# RPi_PICO.net
KiCad netlist of a schematic drawn in Altium Designer
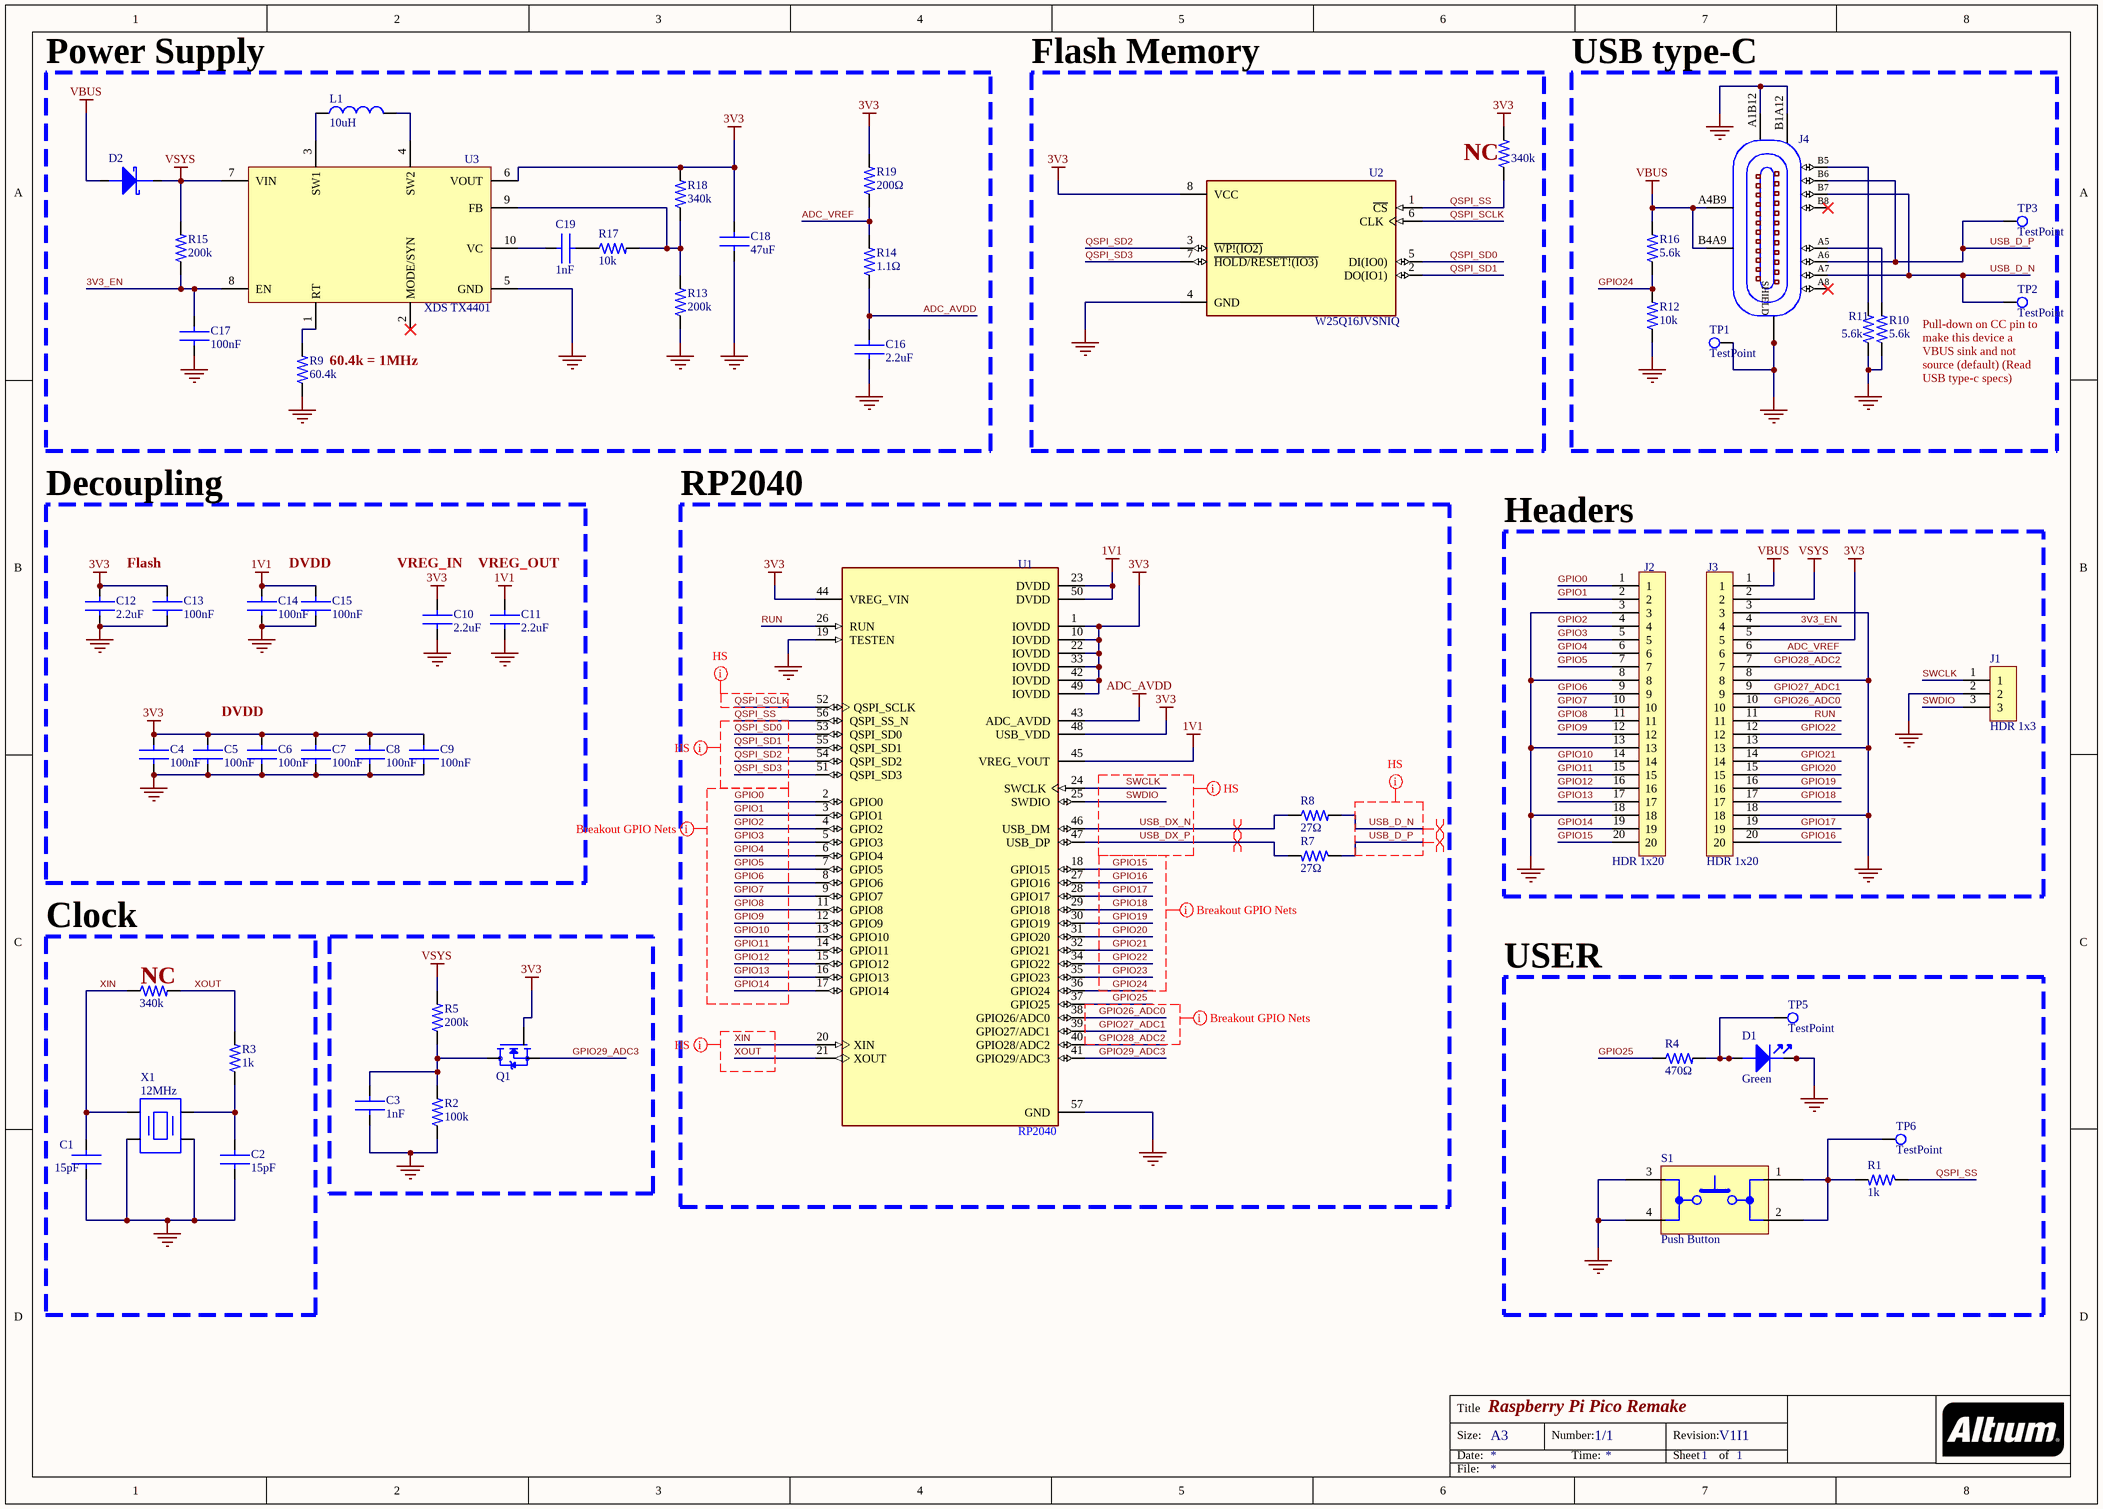
[diagram p0: RPi_PICO.SchDoc]

(export (version "E")
  (design (tool "Eeschema 10.0.6"))
  (components
    (comp (ref "C1")
      (value "15pF")
      (footprint "MLCC-0201")
      (description "15pF ±5% 50V 0201 C0G MLCC - SMD/SMT ROHS")
      (libsource (lib "RPi_PICO") (part "0201CG150J500NT"))
    )
    (comp (ref "C2")
      (value "15pF")
      (footprint "MLCC-0201")
      (description "15pF ±5% 50V 0201 C0G MLCC - SMD/SMT ROHS")
      (libsource (lib "RPi_PICO") (part "0201CG150J500NT"))
    )
    (comp (ref "C3")
      (value "1nF")
      (footprint "MLCC-0201")
      (description "1nF ±10% 50V 0201  X7R  MLCC - SMD/SMT ROHS")
      (libsource (lib "RPi_PICO") (part "CC0201KRX7R9BB102"))
    )
    (comp (ref "C4")
      (value "100nF")
      (footprint "MLCC-0201")
      (description "100nF ±10% 10V 0201 X5R MLCC - SMD/SMT ROHS")
      (libsource (lib "RPi_PICO") (part "CL03A104KP3NNNC"))
    )
    (comp (ref "C5")
      (value "100nF")
      (footprint "MLCC-0201")
      (description "100nF ±10% 10V 0201 X5R MLCC - SMD/SMT ROHS")
      (libsource (lib "RPi_PICO") (part "CL03A104KP3NNNC"))
    )
    (comp (ref "C6")
      (value "100nF")
      (footprint "MLCC-0201")
      (description "100nF ±10% 10V 0201 X5R MLCC - SMD/SMT ROHS")
      (libsource (lib "RPi_PICO") (part "CL03A104KP3NNNC"))
    )
    (comp (ref "C7")
      (value "100nF")
      (footprint "MLCC-0201")
      (description "100nF ±10% 10V 0201 X5R MLCC - SMD/SMT ROHS")
      (libsource (lib "RPi_PICO") (part "CL03A104KP3NNNC"))
    )
    (comp (ref "C8")
      (value "100nF")
      (footprint "MLCC-0201")
      (description "100nF ±10% 10V 0201 X5R MLCC - SMD/SMT ROHS")
      (libsource (lib "RPi_PICO") (part "CL03A104KP3NNNC"))
    )
    (comp (ref "C9")
      (value "100nF")
      (footprint "MLCC-0201")
      (description "100nF ±10% 10V 0201 X5R MLCC - SMD/SMT ROHS")
      (libsource (lib "RPi_PICO") (part "CL03A104KP3NNNC"))
    )
    (comp (ref "C10")
      (value "2.2uF")
      (footprint "MLCC-0402")
      (description "2.2uF ±20% 6.3V 0402 X5R   MLCC - SMD/SMT ROHS")
      (libsource (lib "RPi_PICO") (part "CL05A225MQ5NSNC"))
    )
    (comp (ref "C11")
      (value "2.2uF")
      (footprint "MLCC-0402")
      (description "2.2uF ±20% 6.3V 0402 X5R   MLCC - SMD/SMT ROHS")
      (libsource (lib "RPi_PICO") (part "CL05A225MQ5NSNC"))
    )
    (comp (ref "C12")
      (value "2.2uF")
      (footprint "MLCC-0402")
      (description "2.2uF ±20% 6.3V 0402 X5R   MLCC - SMD/SMT ROHS")
      (libsource (lib "RPi_PICO") (part "CL05A225MQ5NSNC"))
    )
    (comp (ref "C13")
      (value "100nF")
      (footprint "MLCC-0201")
      (description "100nF ±10% 10V 0201 X5R MLCC - SMD/SMT ROHS")
      (libsource (lib "RPi_PICO") (part "CL03A104KP3NNNC"))
    )
    (comp (ref "C14")
      (value "100nF")
      (footprint "MLCC-0201")
      (description "100nF ±10% 10V 0201 X5R MLCC - SMD/SMT ROHS")
      (libsource (lib "RPi_PICO") (part "CL03A104KP3NNNC"))
    )
    (comp (ref "C15")
      (value "100nF")
      (footprint "MLCC-0201")
      (description "100nF ±10% 10V 0201 X5R MLCC - SMD/SMT ROHS")
      (libsource (lib "RPi_PICO") (part "CL03A104KP3NNNC"))
    )
    (comp (ref "C16")
      (value "2.2uF")
      (footprint "MLCC-0402")
      (description "2.2uF ±20% 6.3V 0402 X5R   MLCC - SMD/SMT ROHS")
      (libsource (lib "RPi_PICO") (part "CL05A225MQ5NSNC"))
    )
    (comp (ref "C17")
      (value "100nF")
      (footprint "MLCC-0201")
      (description "100nF ±10% 10V 0201 X5R MLCC - SMD/SMT ROHS")
      (libsource (lib "RPi_PICO") (part "CL03A104KP3NNNC"))
    )
    (comp (ref "C18")
      (value "47uF")
      (footprint "Ceramic_0805")
      (description "47uF 6.3V ±20% 0805   X5R MLCC - SMD/SMT ROHS")
      (libsource (lib "RPi_PICO") (part "CL21A476MQYNNNE"))
    )
    (comp (ref "C19")
      (value "1nF")
      (footprint "MLCC-0201")
      (description "1nF ±10% 50V 0201  X7R  MLCC - SMD/SMT ROHS")
      (libsource (lib "RPi_PICO") (part "CC0201KRX7R9BB102"))
    )
    (comp (ref "D1")
      (value "Green")
      (footprint "LED-0603")
      (libsource (lib "RPi_PICO") (part "19-217/GHC-YR1S2/3T"))
    )
    (comp (ref "D2")
      (value "Schottky")
      (footprint "SOD-123F")
      (description "Diode Schottky 20 V 1A Surface Mount SOD-123FL")
      (libsource (lib "HUZZAH32") (part "RB161MM-20CT-ND"))
    )
    (comp (ref "J1")
      (value "HDR 1x3")
      (footprint "CONN-3-SMD+THT")
      (description "HDR 1x3 2.54mm double SMD+THT")
      (libsource (lib "RPi_PICO") (part "HDR 1x3 2.54mm double"))
    )
    (comp (ref "J2")
      (value "HDR 1x20")
      (footprint "Conn-20-SMD+THT")
      (description "HDR 1x20 2.54mm double SMD+THT")
      (libsource (lib "RPi_PICO") (part "HDR 1x20 2.54mm double"))
    )
    (comp (ref "J3")
      (value "HDR 1x20")
      (footprint "Conn-20-SMD+THT")
      (description "HDR 1x20 2.54mm double SMD+THT")
      (libsource (lib "") (part "HDR 1x20 2.54mm double_1"))
    )
    (comp (ref "J4")
      (value "USB-type-c")
      (footprint "USB-type-c-31-M-12")
      (description "250mA 1 16 Female Type-C SMD USB Connectors ROHS")
      (libsource (lib "RPi_PICO") (part "USB-type-c"))
    )
    (comp (ref "L1")
      (value "10uH")
      (footprint "L-1515-SMD")
      (description "1.7A 10uH ±20% 2.5A 165mΩ - Inductors (SMD) ROHS")
      (libsource (lib "RPi_PICO") (part "FDSD0420-H-100M=P3"))
    )
    (comp (ref "Q1") (value "N-MOS") (footprint "SOT-523") (libsource (lib "RPi_PICO") (part "TPCJ1012")))
    (comp (ref "R1") (value "1k") (footprint "R-0402") (libsource (lib "RPi_PICO") (part "0402WGF1001TCE")))
    (comp (ref "R2") (value "100k") (footprint "R-0402") (libsource (lib "RPi_PICO") (part "0402WGF1003TCE")))
    (comp (ref "R3") (value "1k") (footprint "R-0402") (libsource (lib "RPi_PICO") (part "0402WGF1001TCE")))
    (comp (ref "R4") (value "470Ω") (footprint "R-0402") (libsource (lib "RPi_PICO") (part "0402WGF4700TCE")))
    (comp (ref "R5") (value "200k") (footprint "R-0402") (libsource (lib "RPi_PICO") (part "0402WGF2003TCE")))
    (comp (ref "R6") (value "340k") (footprint "R-0402") (libsource (lib "RPi_PICO") (part "WR04X3403FTL")))
    (comp (ref "R7") (value "27Ω") (footprint "R-0201") (libsource (lib "RPi_PICO") (part "RC0201JR-0727RL")))
    (comp (ref "R8") (value "27Ω") (footprint "R-0201") (libsource (lib "RPi_PICO") (part "RC0201JR-0727RL")))
    (comp (ref "R9")
      (value "60.4k")
      (footprint "R-0402")
      (libsource (lib "RPi_PICO") (part "0402WGF6042TCE"))
    )
    (comp (ref "R10")
      (value "5.6k")
      (footprint "R-0402")
      (libsource (lib "RPi_PICO") (part "0402WGF5601TCE"))
    )
    (comp (ref "R11")
      (value "5.6k")
      (footprint "R-0402")
      (libsource (lib "RPi_PICO") (part "0402WGF5601TCE"))
    )
    (comp (ref "R12")
      (value "10k")
      (footprint "R-0402")
      (libsource (lib "RPi_PICO") (part "RC0402FR-0710KL"))
    )
    (comp (ref "R13")
      (value "200k")
      (footprint "R-0402")
      (libsource (lib "RPi_PICO") (part "0402WGF2003TCE"))
    )
    (comp (ref "R14")
      (value "1.1Ω")
      (footprint "R-0402")
      (libsource (lib "RPi_PICO") (part "0402WGJ011JTCE"))
    )
    (comp (ref "R15")
      (value "200k")
      (footprint "R-0402")
      (libsource (lib "RPi_PICO") (part "0402WGF2003TCE"))
    )
    (comp (ref "R16")
      (value "5.6k")
      (footprint "R-0402")
      (libsource (lib "RPi_PICO") (part "0402WGF5601TCE"))
    )
    (comp (ref "R17")
      (value "10k")
      (footprint "R-0402")
      (libsource (lib "RPi_PICO") (part "RC0402FR-0710KL"))
    )
    (comp (ref "R18") (value "340k") (footprint "R-0402") (libsource (lib "RPi_PICO") (part "WR04X3403FTL")))
    (comp (ref "R19")
      (value "200Ω")
      (footprint "R_0603")
      (libsource (lib "RPi_PICO") (part "0603WAF2000T5E"))
    )
    (comp (ref "R20") (value "340k") (footprint "R-0402") (libsource (lib "RPi_PICO") (part "WR04X3403FTL")))
    (comp (ref "S1")
      (value "Push Button")
      (footprint "SW_PB_6643")
      (description "SPST tactile switch SMD 6x6x4.3mm")
      (libsource (lib "HUZZAH32") (part "GT-TC089B-H043-L1"))
    )
    (comp (ref "TP1")
      (value "TestPoint")
      (footprint "TestPoint-60mil-rectangle")
      (libsource (lib "RPi_PICO") (part "TestPoint"))
    )
    (comp (ref "TP2")
      (value "TestPoint")
      (footprint "TestPoint-60mil-rectangle")
      (libsource (lib "RPi_PICO") (part "TestPoint"))
    )
    (comp (ref "TP3")
      (value "TestPoint")
      (footprint "TestPoint-60mil-rectangle")
      (libsource (lib "RPi_PICO") (part "TestPoint"))
    )
    (comp (ref "TP5")
      (value "TestPoint")
      (footprint "TestPoint-60mil-rectangle")
      (libsource (lib "RPi_PICO") (part "TestPoint"))
    )
    (comp (ref "TP6")
      (value "TestPoint")
      (footprint "TestPoint-60mil-rectangle")
      (libsource (lib "RPi_PICO") (part "TestPoint"))
    )
    (comp (ref "U1") (value "RP2040") (footprint "QFN56-RP2040") (libsource (lib "RPi_PICO") (part "RP2040")))
    (comp (ref "U2")
      (value "W25Q16JVSNIQ")
      (footprint "SOIC-8")
      (description "FLASH - NOR Memory IC 16Mb (2M x 8) SPI - Quad I/O 133 MHz SOIC-8")
      (libsource (lib "RPi_PICO") (part "W25Q16JVSNIQ"))
    )
    (comp (ref "U3")
      (value "XDS TX4401")
      (footprint "MSOP-10L")
      (description "Buck-boost type -40℃~+85℃ 1 1.8V~5.5V 2.5V~5.5V 1A 1uA MSOP-10L DC-DC Converters ROHS")
      (libsource (lib "RPi_PICO") (part "XDS-TX4401"))
    )
    (comp (ref "X1")
      (value "12MHz")
      (footprint "XTAL-SMD-3.2mm-2.5mm")
      (description "12MHz HCMOS 1.8V~3.3V -20℃~+70℃ ±30ppm  SMD3225-4P Oscillators ROHS")
      (libsource (lib "RPi_PICO") (part "HCI CO32H4-12.000-WPJHPSN"))
    )
  )
  (nets
    (net (code "1") (name "/3V3_EN") (class "Default")
      (node (ref "C17") (pin "2") (pinfunction "2_2") (pintype "passive"))
      (node (ref "J3") (pin "4") (pinfunction "4_4") (pintype "passive"))
      (node (ref "R15") (pin "1") (pinfunction "1_1") (pintype "passive"))
      (node (ref "U3") (pin "8") (pinfunction "EN_8") (pintype "passive"))
    )
    (net (code "2") (name "/ADC_VREF") (class "Default")
      (node (ref "J3") (pin "6") (pinfunction "6_6") (pintype "passive"))
      (node (ref "R14") (pin "2") (pinfunction "2_2") (pintype "passive"))
      (node (ref "R19") (pin "1") (pinfunction "1_1") (pintype "passive"))
    )
    (net (code "3") (name "/GPIO0") (class "Default")
      (node (ref "J2") (pin "1") (pinfunction "1_1") (pintype "passive"))
      (node (ref "U1") (pin "2") (pinfunction "GPIO0_2") (pintype "bidirectional"))
    )
    (net (code "4") (name "/GPIO1") (class "Default")
      (node (ref "J2") (pin "2") (pinfunction "2_2") (pintype "passive"))
      (node (ref "U1") (pin "3") (pinfunction "GPIO1_3") (pintype "bidirectional"))
    )
    (net (code "5") (name "/GPIO2") (class "Default")
      (node (ref "J2") (pin "4") (pinfunction "4_4") (pintype "passive"))
      (node (ref "U1") (pin "4") (pinfunction "GPIO2_4") (pintype "bidirectional"))
    )
    (net (code "6") (name "/GPIO3") (class "Default")
      (node (ref "J2") (pin "5") (pinfunction "5_5") (pintype "passive"))
      (node (ref "U1") (pin "5") (pinfunction "GPIO3_5") (pintype "bidirectional"))
    )
    (net (code "7") (name "/GPIO4") (class "Default")
      (node (ref "J2") (pin "6") (pinfunction "6_6") (pintype "passive"))
      (node (ref "U1") (pin "6") (pinfunction "GPIO4_6") (pintype "bidirectional"))
    )
    (net (code "8") (name "/GPIO5") (class "Default")
      (node (ref "J2") (pin "7") (pinfunction "7_7") (pintype "passive"))
      (node (ref "U1") (pin "7") (pinfunction "GPIO5_7") (pintype "bidirectional"))
    )
    (net (code "9") (name "/GPIO6") (class "Default")
      (node (ref "J2") (pin "9") (pinfunction "9_9") (pintype "passive"))
      (node (ref "U1") (pin "8") (pinfunction "GPIO6_8") (pintype "bidirectional"))
    )
    (net (code "10") (name "/GPIO7") (class "Default")
      (node (ref "J2") (pin "10") (pinfunction "10_10") (pintype "passive"))
      (node (ref "U1") (pin "9") (pinfunction "GPIO7_9") (pintype "bidirectional"))
    )
    (net (code "11") (name "/GPIO8") (class "Default")
      (node (ref "J2") (pin "11") (pinfunction "11_11") (pintype "passive"))
      (node (ref "U1") (pin "11") (pinfunction "GPIO8_11") (pintype "bidirectional"))
    )
    (net (code "12") (name "/GPIO9") (class "Default")
      (node (ref "J2") (pin "12") (pinfunction "12_12") (pintype "passive"))
      (node (ref "U1") (pin "12") (pinfunction "GPIO9_12") (pintype "bidirectional"))
    )
    (net (code "13") (name "/GPIO10") (class "Default")
      (node (ref "J2") (pin "14") (pinfunction "14_14") (pintype "passive"))
      (node (ref "U1") (pin "13") (pinfunction "GPIO10_13") (pintype "bidirectional"))
    )
    (net (code "14") (name "/GPIO11") (class "Default")
      (node (ref "J2") (pin "15") (pinfunction "15_15") (pintype "passive"))
      (node (ref "U1") (pin "14") (pinfunction "GPIO11_14") (pintype "bidirectional"))
    )
    (net (code "15") (name "/GPIO12") (class "Default")
      (node (ref "J2") (pin "16") (pinfunction "16_16") (pintype "passive"))
      (node (ref "U1") (pin "15") (pinfunction "GPIO12_15") (pintype "bidirectional"))
    )
    (net (code "16") (name "/GPIO13") (class "Default")
      (node (ref "J2") (pin "17") (pinfunction "17_17") (pintype "passive"))
      (node (ref "U1") (pin "16") (pinfunction "GPIO13_16") (pintype "bidirectional"))
    )
    (net (code "17") (name "/GPIO14") (class "Default")
      (node (ref "J2") (pin "19") (pinfunction "19_19") (pintype "passive"))
      (node (ref "U1") (pin "17") (pinfunction "GPIO14_17") (pintype "bidirectional"))
    )
    (net (code "18") (name "/GPIO15") (class "Default")
      (node (ref "J2") (pin "20") (pinfunction "20_20") (pintype "passive"))
      (node (ref "U1") (pin "18") (pinfunction "GPIO15_18") (pintype "bidirectional"))
    )
    (net (code "19") (name "/GPIO16") (class "Default")
      (node (ref "J3") (pin "20") (pinfunction "20_20") (pintype "passive"))
      (node (ref "U1") (pin "27") (pinfunction "GPIO16_27") (pintype "bidirectional"))
    )
    (net (code "20") (name "/GPIO17") (class "Default")
      (node (ref "J3") (pin "19") (pinfunction "19_19") (pintype "passive"))
      (node (ref "U1") (pin "28") (pinfunction "GPIO17_28") (pintype "bidirectional"))
    )
    (net (code "21") (name "/GPIO18") (class "Default")
      (node (ref "J3") (pin "17") (pinfunction "17_17") (pintype "passive"))
      (node (ref "U1") (pin "29") (pinfunction "GPIO18_29") (pintype "bidirectional"))
    )
    (net (code "22") (name "/GPIO19") (class "Default")
      (node (ref "J3") (pin "16") (pinfunction "16_16") (pintype "passive"))
      (node (ref "U1") (pin "30") (pinfunction "GPIO19_30") (pintype "bidirectional"))
    )
    (net (code "23") (name "/GPIO20") (class "Default")
      (node (ref "J3") (pin "15") (pinfunction "15_15") (pintype "passive"))
      (node (ref "U1") (pin "31") (pinfunction "GPIO20_31") (pintype "bidirectional"))
    )
    (net (code "24") (name "/GPIO21") (class "Default")
      (node (ref "J3") (pin "14") (pinfunction "14_14") (pintype "passive"))
      (node (ref "U1") (pin "32") (pinfunction "GPIO21_32") (pintype "bidirectional"))
    )
    (net (code "25") (name "/GPIO22") (class "Default")
      (node (ref "J3") (pin "12") (pinfunction "12_12") (pintype "passive"))
      (node (ref "U1") (pin "34") (pinfunction "GPIO22_34") (pintype "bidirectional"))
    )
    (net (code "26") (name "/GPIO23") (class "Default")
      (node (ref "U1") (pin "35") (pinfunction "GPIO23_35") (pintype "bidirectional"))
    )
    (net (code "27") (name "/GPIO24") (class "Default")
      (node (ref "R12") (pin "2") (pinfunction "2_2") (pintype "passive"))
      (node (ref "R16") (pin "1") (pinfunction "1_1") (pintype "passive"))
      (node (ref "U1") (pin "36") (pinfunction "GPIO24_36") (pintype "bidirectional"))
    )
    (net (code "28") (name "/GPIO25") (class "Default")
      (node (ref "R4") (pin "1") (pinfunction "1_1") (pintype "passive"))
      (node (ref "U1") (pin "37") (pinfunction "GPIO25_37") (pintype "bidirectional"))
    )
    (net (code "29") (name "/GPIO26_ADC0") (class "Default")
      (node (ref "J3") (pin "10") (pinfunction "10_10") (pintype "passive"))
      (node (ref "U1") (pin "38") (pinfunction "GPIO26/ADC0_38") (pintype "bidirectional"))
    )
    (net (code "30") (name "/GPIO27_ADC1") (class "Default")
      (node (ref "J3") (pin "9") (pinfunction "9_9") (pintype "passive"))
      (node (ref "U1") (pin "39") (pinfunction "GPIO27/ADC1_39") (pintype "bidirectional"))
    )
    (net (code "31") (name "/GPIO28_ADC2") (class "Default")
      (node (ref "J3") (pin "7") (pinfunction "7_7") (pintype "passive"))
      (node (ref "U1") (pin "40") (pinfunction "GPIO28/ADC2_40") (pintype "bidirectional"))
    )
    (net (code "32") (name "/GPIO29_ADC3") (class "Default")
      (node (ref "Q1") (pin "3") (pinfunction "S_3") (pintype "passive"))
      (node (ref "U1") (pin "41") (pinfunction "GPIO29/ADC3_41") (pintype "bidirectional"))
    )
    (net (code "33") (name "/QSPI_SCLK") (class "Default")
      (node (ref "U1") (pin "52") (pinfunction "QSPI_SCLK_52") (pintype "bidirectional"))
      (node (ref "U2") (pin "6") (pinfunction "CLK_6") (pintype "input"))
    )
    (net (code "34") (name "/QSPI_SD0") (class "Default")
      (node (ref "U1") (pin "53") (pinfunction "QSPI_SD0_53") (pintype "bidirectional"))
      (node (ref "U2") (pin "5") (pinfunction "DI(IO0)_5") (pintype "bidirectional"))
    )
    (net (code "35") (name "/QSPI_SD1") (class "Default")
      (node (ref "U1") (pin "55") (pinfunction "QSPI_SD1_55") (pintype "bidirectional"))
      (node (ref "U2") (pin "2") (pinfunction "DO(IO1)_2") (pintype "bidirectional"))
    )
    (net (code "36") (name "/QSPI_SD2") (class "Default")
      (node (ref "U1") (pin "54") (pinfunction "QSPI_SD2_54") (pintype "bidirectional"))
      (node (ref "U2") (pin "3") (pinfunction "~{WP!(IO2)}_3") (pintype "bidirectional"))
    )
    (net (code "37") (name "/QSPI_SD3") (class "Default")
      (node (ref "U1") (pin "51") (pinfunction "QSPI_SD3_51") (pintype "bidirectional"))
      (node (ref "U2") (pin "7") (pinfunction "~{HOLD/RESET!(IO3)}_7") (pintype "bidirectional"))
    )
    (net (code "38") (name "/QSPI_SS") (class "Default")
      (node (ref "R1") (pin "1") (pinfunction "1_1") (pintype "passive"))
      (node (ref "R20") (pin "1") (pinfunction "1_1") (pintype "passive"))
      (node (ref "U1") (pin "56") (pinfunction "QSPI_SS_N_56") (pintype "bidirectional"))
      (node (ref "U2") (pin "1") (pinfunction "~{CS}_1") (pintype "input"))
    )
    (net (code "39") (name "/RUN") (class "Default")
      (node (ref "J3") (pin "11") (pinfunction "11_11") (pintype "passive"))
      (node (ref "U1") (pin "26") (pinfunction "RUN_26") (pintype "input"))
    )
    (net (code "40") (name "/SWCLK") (class "Default")
      (node (ref "J1") (pin "1") (pinfunction "1_1") (pintype "passive"))
      (node (ref "U1") (pin "24") (pinfunction "SWCLK_24") (pintype "input"))
    )
    (net (code "41") (name "/SWDIO") (class "Default")
      (node (ref "J1") (pin "3") (pinfunction "3_3") (pintype "passive"))
      (node (ref "U1") (pin "25") (pinfunction "SWDIO_25") (pintype "bidirectional"))
    )
    (net (code "42") (name "/USB_DX_N") (class "Default")
      (node (ref "R8") (pin "1") (pinfunction "1_1") (pintype "passive"))
      (node (ref "U1") (pin "46") (pinfunction "USB_DM_46") (pintype "bidirectional"))
    )
    (net (code "43") (name "/USB_DX_P") (class "Default")
      (node (ref "R7") (pin "2") (pinfunction "2_2") (pintype "passive"))
      (node (ref "U1") (pin "47") (pinfunction "USB_DP_47") (pintype "bidirectional"))
    )
    (net (code "44") (name "/USB_D_N") (class "Default")
      (node (ref "J4") (pin "A7") (pinfunction "DN1_A7") (pintype "bidirectional"))
      (node (ref "J4") (pin "B7") (pinfunction "DN2_B7") (pintype "bidirectional"))
      (node (ref "R8") (pin "2") (pinfunction "2_2") (pintype "passive"))
      (node (ref "TP2") (pin "1") (pinfunction "1_1") (pintype "passive"))
    )
    (net (code "45") (name "/USB_D_P") (class "Default")
      (node (ref "J4") (pin "A6") (pinfunction "DP1_A6") (pintype "bidirectional"))
      (node (ref "J4") (pin "B6") (pinfunction "DP2_B6") (pintype "bidirectional"))
      (node (ref "R7") (pin "1") (pinfunction "1_1") (pintype "passive"))
      (node (ref "TP3") (pin "1") (pinfunction "1_1") (pintype "passive"))
    )
    (net (code "46") (name "/XIN") (class "Default")
      (node (ref "C1") (pin "2") (pinfunction "2_2") (pintype "passive"))
      (node (ref "R6") (pin "1") (pinfunction "1_1") (pintype "passive"))
      (node (ref "U1") (pin "20") (pinfunction "XIN_20") (pintype "input"))
      (node (ref "X1") (pin "1") (pinfunction "1_1") (pintype "passive"))
    )
    (net (code "47") (name "/XOUT") (class "Default")
      (node (ref "R3") (pin "2") (pinfunction "2_2") (pintype "passive"))
      (node (ref "R6") (pin "2") (pinfunction "2_2") (pintype "passive"))
      (node (ref "U1") (pin "21") (pinfunction "XOUT_21") (pintype "output"))
    )
    (net (code "48") (name "1V1") (class "Default")
      (node (ref "C11") (pin "2") (pinfunction "2_2") (pintype "passive"))
      (node (ref "C14") (pin "2") (pinfunction "2_2") (pintype "passive"))
      (node (ref "C15") (pin "2") (pinfunction "2_2") (pintype "passive"))
      (node (ref "U1") (pin "23") (pinfunction "DVDD_23") (pintype "power_in"))
      (node (ref "U1") (pin "45") (pinfunction "VREG_VOUT_45") (pintype "power_in"))
      (node (ref "U1") (pin "50") (pinfunction "DVDD_50") (pintype "power_in"))
    )
    (net (code "49") (name "3V3") (class "Default")
      (node (ref "C10") (pin "2") (pinfunction "2_2") (pintype "passive"))
      (node (ref "C12") (pin "2") (pinfunction "2_2") (pintype "passive"))
      (node (ref "C13") (pin "2") (pinfunction "2_2") (pintype "passive"))
      (node (ref "C18") (pin "2") (pinfunction "2_2") (pintype "passive"))
      (node (ref "C4") (pin "2") (pinfunction "2_2") (pintype "passive"))
      (node (ref "C5") (pin "2") (pinfunction "2_2") (pintype "passive"))
      (node (ref "C6") (pin "2") (pinfunction "2_2") (pintype "passive"))
      (node (ref "C7") (pin "2") (pinfunction "2_2") (pintype "passive"))
      (node (ref "C8") (pin "2") (pinfunction "2_2") (pintype "passive"))
      (node (ref "C9") (pin "2") (pinfunction "2_2") (pintype "passive"))
      (node (ref "J3") (pin "5") (pinfunction "5_5") (pintype "passive"))
      (node (ref "Q1") (pin "1") (pinfunction "G_1") (pintype "passive"))
      (node (ref "R18") (pin "2") (pinfunction "2_2") (pintype "passive"))
      (node (ref "R19") (pin "2") (pinfunction "2_2") (pintype "passive"))
      (node (ref "R20") (pin "2") (pinfunction "2_2") (pintype "passive"))
      (node (ref "U1") (pin "1") (pinfunction "IOVDD_1") (pintype "power_in"))
      (node (ref "U1") (pin "10") (pinfunction "IOVDD_10") (pintype "power_in"))
      (node (ref "U1") (pin "22") (pinfunction "IOVDD_22") (pintype "power_in"))
      (node (ref "U1") (pin "33") (pinfunction "IOVDD_33") (pintype "power_in"))
      (node (ref "U1") (pin "42") (pinfunction "IOVDD_42") (pintype "power_in"))
      (node (ref "U1") (pin "44") (pinfunction "VREG_VIN_44") (pintype "power_in"))
      (node (ref "U1") (pin "48") (pinfunction "USB_VDD_48") (pintype "power_in"))
      (node (ref "U1") (pin "49") (pinfunction "IOVDD_49") (pintype "power_in"))
      (node (ref "U2") (pin "8") (pinfunction "VCC_8") (pintype "power_in"))
      (node (ref "U3") (pin "6") (pinfunction "VOUT_6") (pintype "passive"))
    )
    (net (code "50") (name "ADC_AVDD") (class "Default")
      (node (ref "C16") (pin "2") (pinfunction "2_2") (pintype "passive"))
      (node (ref "R14") (pin "1") (pinfunction "1_1") (pintype "passive"))
      (node (ref "U1") (pin "43") (pinfunction "ADC_AVDD_43") (pintype "power_in"))
    )
    (net (code "51") (name "GND") (class "Default")
      (node (ref "C1") (pin "1") (pinfunction "1_1") (pintype "passive"))
      (node (ref "C10") (pin "1") (pinfunction "1_1") (pintype "passive"))
      (node (ref "C11") (pin "1") (pinfunction "1_1") (pintype "passive"))
      (node (ref "C12") (pin "1") (pinfunction "1_1") (pintype "passive"))
      (node (ref "C13") (pin "1") (pinfunction "1_1") (pintype "passive"))
      (node (ref "C14") (pin "1") (pinfunction "1_1") (pintype "passive"))
      (node (ref "C15") (pin "1") (pinfunction "1_1") (pintype "passive"))
      (node (ref "C16") (pin "1") (pinfunction "1_1") (pintype "passive"))
      (node (ref "C17") (pin "1") (pinfunction "1_1") (pintype "passive"))
      (node (ref "C18") (pin "1") (pinfunction "1_1") (pintype "passive"))
      (node (ref "C2") (pin "1") (pinfunction "1_1") (pintype "passive"))
      (node (ref "C3") (pin "1") (pinfunction "1_1") (pintype "passive"))
      (node (ref "C4") (pin "1") (pinfunction "1_1") (pintype "passive"))
      (node (ref "C5") (pin "1") (pinfunction "1_1") (pintype "passive"))
      (node (ref "C6") (pin "1") (pinfunction "1_1") (pintype "passive"))
      (node (ref "C7") (pin "1") (pinfunction "1_1") (pintype "passive"))
      (node (ref "C8") (pin "1") (pinfunction "1_1") (pintype "passive"))
      (node (ref "C9") (pin "1") (pinfunction "1_1") (pintype "passive"))
      (node (ref "D1") (pin "2") (pinfunction "C_2") (pintype "passive"))
      (node (ref "J1") (pin "2") (pinfunction "2_2") (pintype "passive"))
      (node (ref "J2") (pin "13") (pinfunction "13_13") (pintype "passive"))
      (node (ref "J2") (pin "18") (pinfunction "18_18") (pintype "passive"))
      (node (ref "J2") (pin "3") (pinfunction "3_3") (pintype "passive"))
      (node (ref "J2") (pin "8") (pinfunction "8_8") (pintype "passive"))
      (node (ref "J3") (pin "13") (pinfunction "13_13") (pintype "passive"))
      (node (ref "J3") (pin "18") (pinfunction "18_18") (pintype "passive"))
      (node (ref "J3") (pin "3") (pinfunction "3_3") (pintype "passive"))
      (node (ref "J3") (pin "8") (pinfunction "8_8") (pintype "passive"))
      (node (ref "J4") (pin "A1B12") (pinfunction "GND_A1B12") (pintype "power_in"))
      (node (ref "J4") (pin "B1A12") (pinfunction "GND_B1A12") (pintype "power_in"))
      (node (ref "J4") (pin "S1") (pinfunction "SHIELD_S1") (pintype "passive"))
      (node (ref "J4") (pin "S2") (pinfunction "SHIELD_S2") (pintype "passive"))
      (node (ref "J4") (pin "S3") (pinfunction "SHIELD_S3") (pintype "passive"))
      (node (ref "J4") (pin "S4") (pinfunction "SHIELD_S4") (pintype "passive"))
      (node (ref "R10") (pin "1") (pinfunction "1_1") (pintype "passive"))
      (node (ref "R11") (pin "1") (pinfunction "1_1") (pintype "passive"))
      (node (ref "R12") (pin "1") (pinfunction "1_1") (pintype "passive"))
      (node (ref "R13") (pin "1") (pinfunction "1_1") (pintype "passive"))
      (node (ref "R2") (pin "1") (pinfunction "1_1") (pintype "passive"))
      (node (ref "R9") (pin "1") (pinfunction "1_1") (pintype "passive"))
      (node (ref "S1") (pin "3") (pinfunction "3_3") (pintype "passive"))
      (node (ref "S1") (pin "4") (pinfunction "4_4") (pintype "passive"))
      (node (ref "TP1") (pin "1") (pinfunction "1_1") (pintype "passive"))
      (node (ref "U1") (pin "19") (pinfunction "TESTEN_19") (pintype "input"))
      (node (ref "U1") (pin "57") (pinfunction "GND_57") (pintype "power_in"))
      (node (ref "U2") (pin "4") (pinfunction "GND_4") (pintype "power_in"))
      (node (ref "U3") (pin "5") (pinfunction "GND_5") (pintype "passive"))
      (node (ref "X1") (pin "2") (pinfunction "2_2") (pintype "passive"))
      (node (ref "X1") (pin "4") (pinfunction "4_4") (pintype "passive"))
    )
    (net (code "52") (name "Net-(C2-Pad2)") (class "Default")
      (node (ref "C2") (pin "2") (pinfunction "2_2") (pintype "passive"))
      (node (ref "R3") (pin "1") (pinfunction "1_1") (pintype "passive"))
      (node (ref "X1") (pin "3") (pinfunction "3_3") (pintype "passive"))
    )
    (net (code "53") (name "Net-(C19-Pad2)") (class "Default")
      (node (ref "C19") (pin "2") (pinfunction "2_2") (pintype "passive"))
      (node (ref "R17") (pin "1") (pinfunction "1_1") (pintype "passive"))
    )
    (net (code "54") (name "Net-(D1-A)") (class "Default")
      (node (ref "D1") (pin "1") (pinfunction "A_1") (pintype "passive"))
      (node (ref "R4") (pin "2") (pinfunction "2_2") (pintype "passive"))
      (node (ref "TP5") (pin "1") (pinfunction "1_1") (pintype "passive"))
    )
    (net (code "55") (name "Net-(J4-CC1)") (class "Default")
      (node (ref "J4") (pin "A5") (pinfunction "CC1_A5") (pintype "bidirectional"))
      (node (ref "R10") (pin "2") (pinfunction "2_2") (pintype "passive"))
    )
    (net (code "56") (name "Net-(J4-CC2)") (class "Default")
      (node (ref "J4") (pin "B5") (pinfunction "CC2_B5") (pintype "bidirectional"))
      (node (ref "R11") (pin "2") (pinfunction "2_2") (pintype "passive"))
    )
    (net (code "57") (name "Net-(Q1-D)") (class "Default")
      (node (ref "C3") (pin "2") (pinfunction "2_2") (pintype "passive"))
      (node (ref "Q1") (pin "2") (pinfunction "D_2") (pintype "passive"))
      (node (ref "R2") (pin "2") (pinfunction "2_2") (pintype "passive"))
      (node (ref "R5") (pin "1") (pinfunction "1_1") (pintype "passive"))
    )
    (net (code "58") (name "Net-(R1-Pad2)") (class "Default")
      (node (ref "R1") (pin "2") (pinfunction "2_2") (pintype "passive"))
      (node (ref "S1") (pin "1") (pinfunction "1_1") (pintype "passive"))
      (node (ref "S1") (pin "2") (pinfunction "2_2") (pintype "passive"))
      (node (ref "TP6") (pin "1") (pinfunction "1_1") (pintype "passive"))
    )
    (net (code "59") (name "Net-(U3-FB)") (class "Default")
      (node (ref "R13") (pin "2") (pinfunction "2_2") (pintype "passive"))
      (node (ref "R17") (pin "2") (pinfunction "2_2") (pintype "passive"))
      (node (ref "R18") (pin "1") (pinfunction "1_1") (pintype "passive"))
      (node (ref "U3") (pin "9") (pinfunction "FB_9") (pintype "passive"))
    )
    (net (code "60") (name "Net-(U3-RT)") (class "Default")
      (node (ref "R9") (pin "2") (pinfunction "2_2") (pintype "passive"))
      (node (ref "U3") (pin "1") (pinfunction "RT_1") (pintype "passive"))
    )
    (net (code "61") (name "Net-(U3-SW1)") (class "Default")
      (node (ref "L1") (pin "1") (pinfunction "1_1") (pintype "passive"))
      (node (ref "U3") (pin "3") (pinfunction "SW1_3") (pintype "passive"))
    )
    (net (code "62") (name "Net-(U3-SW2)") (class "Default")
      (node (ref "L1") (pin "2") (pinfunction "2_2") (pintype "passive"))
      (node (ref "U3") (pin "4") (pinfunction "SW2_4") (pintype "passive"))
    )
    (net (code "63") (name "Net-(U3-VC)") (class "Default")
      (node (ref "C19") (pin "1") (pinfunction "1_1") (pintype "passive"))
      (node (ref "U3") (pin "10") (pinfunction "VC_10") (pintype "passive"))
    )
    (net (code "64") (name "VBUS") (class "Default")
      (node (ref "D2") (pin "1") (pinfunction "A_1") (pintype "passive"))
      (node (ref "J3") (pin "1") (pinfunction "1_1") (pintype "passive"))
      (node (ref "J4") (pin "A4B9") (pinfunction "VBUS_A4B9") (pintype "power_in"))
      (node (ref "J4") (pin "B4A9") (pinfunction "VBUS_B4A9") (pintype "power_in"))
      (node (ref "R16") (pin "2") (pinfunction "2_2") (pintype "passive"))
    )
    (net (code "65") (name "VSYS") (class "Default")
      (node (ref "D2") (pin "2") (pinfunction "C_2") (pintype "passive"))
      (node (ref "J3") (pin "2") (pinfunction "2_2") (pintype "passive"))
      (node (ref "R15") (pin "2") (pinfunction "2_2") (pintype "passive"))
      (node (ref "R5") (pin "2") (pinfunction "2_2") (pintype "passive"))
      (node (ref "U3") (pin "7") (pinfunction "VIN_7") (pintype "passive"))
    )
    (net (code "66") (name "unconnected-(J4-SBU1-PadA8)") (class "Default")
      (node (ref "J4") (pin "A8") (pinfunction "SBU1_A8") (pintype "bidirectional+no_connect"))
    )
    (net (code "67") (name "unconnected-(J4-SBU2-PadB8)") (class "Default")
      (node (ref "J4") (pin "B8") (pinfunction "SBU2_B8") (pintype "bidirectional+no_connect"))
    )
    (net (code "68") (name "unconnected-(U3-MODE{slash}SYN-Pad2)") (class "Default")
      (node (ref "U3") (pin "2") (pinfunction "MODE/SYN_2") (pintype "passive+no_connect"))
    )
  )
)
